# USB.net
KiCad netlist of a schematic drawn in Altium Designer
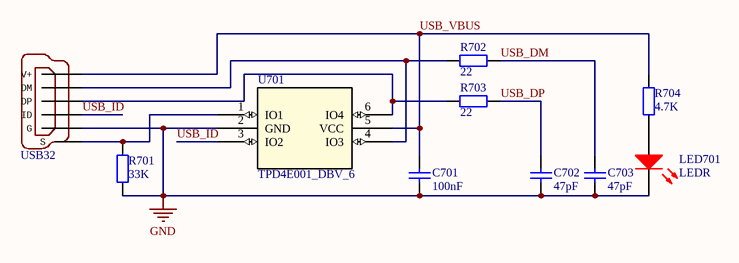
[diagram p0: USB.SchDoc]

(export (version "E")
  (design (tool "Eeschema 10.0.6"))
  (components
    (comp (ref "C701")
      (value "100nF")
      (footprint "0603C")
      (description "MLCC")
      (libsource (lib "Misc") (part "MLCC"))
    )
    (comp (ref "C702")
      (value "47pF")
      (footprint "0603C")
      (description "MLCC")
      (libsource (lib "Misc") (part "MLCC"))
    )
    (comp (ref "C703")
      (value "47pF")
      (footprint "0603C")
      (description "MLCC")
      (libsource (lib "Misc") (part "MLCC"))
    )
    (comp (ref "LED701")
      (value "LEDR")
      (footprint "LED1206R")
      (description "RED LED")
      (libsource (lib "Misc") (part "LEDR"))
    )
    (comp (ref "R701")
      (value "33K")
      (footprint "0603R")
      (description "Resistor")
      (libsource (lib "") (part "Resistor_1"))
    )
    (comp (ref "R702")
      (value "22")
      (footprint "0603R")
      (description "Resistor")
      (libsource (lib "Misc") (part "Resistor"))
    )
    (comp (ref "R703")
      (value "22")
      (footprint "0603R")
      (description "Resistor")
      (libsource (lib "Misc") (part "Resistor"))
    )
    (comp (ref "R704")
      (value "4.7K")
      (footprint "0603R")
      (description "Resistor")
      (libsource (lib "") (part "Resistor_1"))
    )
    (comp (ref "U701")
      (value "TPD4E001_DBV_6")
      (footprint "DBV6")
      (description "Low-Capacitance 4-Channel ESD-Protection for High-Speed Data Interfaces")
      (fields
        (field (name "MANUFACTURER_PART_NUMBER") "tpd4e001_dbv_6")
        (field (name "GENERIC_PART_NUMBER") "TPD4E001")
      )
      (libsource (lib "TPD4E001DBVR") (part "TPD4E001_DBV_6"))
    )
    (comp (ref "USB32")
      (value "MICRO-USB")
      (footprint "USB-MICRO")
      (description "MICRO USB Connector")
      (libsource (lib "Misc") (part "MICRO-USB"))
    )
  )
  (nets
    (net (code "1") (name "/USB_DM") (class "Default")
      (node (ref "C703") (pin "2") (pinfunction "2_2") (pintype "passive"))
      (node (ref "R702") (pin "2") (pinfunction "2_2") (pintype "passive"))
    )
    (net (code "2") (name "/USB_DP") (class "Default")
      (node (ref "C702") (pin "2") (pinfunction "2_2") (pintype "passive"))
      (node (ref "R703") (pin "2") (pinfunction "2_2") (pintype "passive"))
    )
    (net (code "3") (name "/USB_ID") (class "Default")
      (node (ref "U701") (pin "3") (pinfunction "IO2_3") (pintype "bidirectional"))
      (node (ref "USB32") (pin "2") (pinfunction "ID_2") (pintype "passive"))
    )
    (net (code "4") (name "/USB_VBUS") (class "Default")
      (node (ref "C701") (pin "2") (pinfunction "2_2") (pintype "passive"))
      (node (ref "R704") (pin "2") (pinfunction "2_2") (pintype "passive"))
      (node (ref "U701") (pin "5") (pinfunction "VCC_5") (pintype "power_in"))
      (node (ref "USB32") (pin "5") (pinfunction "V+_5") (pintype "passive"))
    )
    (net (code "5") (name "GND") (class "Default")
      (node (ref "C701") (pin "1") (pinfunction "1_1") (pintype "passive"))
      (node (ref "C702") (pin "1") (pinfunction "1_1") (pintype "passive"))
      (node (ref "C703") (pin "1") (pinfunction "1_1") (pintype "passive"))
      (node (ref "LED701") (pin "2") (pinfunction "K_2") (pintype "passive"))
      (node (ref "R701") (pin "1") (pinfunction "1_1") (pintype "passive"))
      (node (ref "U701") (pin "2") (pinfunction "GND_2") (pintype "power_in"))
      (node (ref "USB32") (pin "1") (pinfunction "G_1") (pintype "passive"))
    )
    (net (code "6") (name "Net-(LED701-A)") (class "Default")
      (node (ref "LED701") (pin "1") (pinfunction "A_1") (pintype "passive"))
      (node (ref "R704") (pin "1") (pinfunction "1_1") (pintype "passive"))
    )
    (net (code "7") (name "Net-(U701-IO1)") (class "Default")
      (node (ref "R701") (pin "2") (pinfunction "2_2") (pintype "passive"))
      (node (ref "U701") (pin "1") (pinfunction "IO1_1") (pintype "bidirectional"))
      (node (ref "USB32") (pin "6") (pinfunction "S_6") (pintype "passive"))
    )
    (net (code "8") (name "Net-(U701-IO3)") (class "Default")
      (node (ref "R702") (pin "1") (pinfunction "1_1") (pintype "passive"))
      (node (ref "U701") (pin "4") (pinfunction "IO3_4") (pintype "bidirectional"))
      (node (ref "USB32") (pin "4") (pinfunction "DM_4") (pintype "passive"))
    )
    (net (code "9") (name "Net-(U701-IO4)") (class "Default")
      (node (ref "R703") (pin "1") (pinfunction "1_1") (pintype "passive"))
      (node (ref "U701") (pin "6") (pinfunction "IO4_6") (pintype "bidirectional"))
      (node (ref "USB32") (pin "3") (pinfunction "DP_3") (pintype "passive"))
    )
  )
)
